# MOTOR_DRIVER_L298N.net
KiCad netlist of a schematic drawn in EAGLE
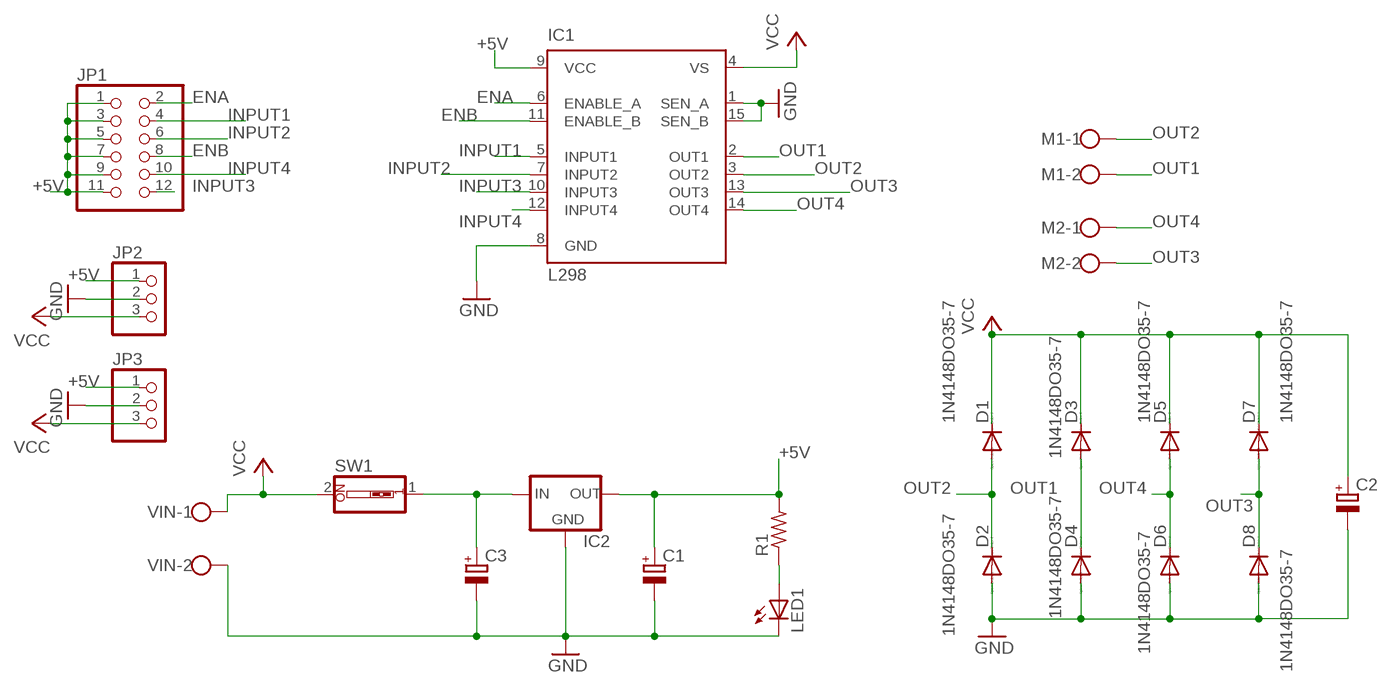
[diagram p0: schematic, sheet 1]

(export (version "E")
  (design (tool "Eeschema 10.0.6"))
  (components
    (comp (ref "C1")
      (value "CPOL-EUE5-6")
      (footprint "eagle-import:E5-6")
      (libsource (lib "eagle-import") (part "CPOL-EUE5-6"))
    )
    (comp (ref "C2")
      (value "CPOL-EUE5-6")
      (footprint "eagle-import:E5-6")
      (libsource (lib "eagle-import") (part "CPOL-EUE5-6"))
    )
    (comp (ref "C3")
      (value "CPOL-EUE5-6")
      (footprint "eagle-import:E5-6")
      (libsource (lib "eagle-import") (part "CPOL-EUE5-6"))
    )
    (comp (ref "D1")
      (value "1N4148DO35-7")
      (footprint "eagle-import:DO35-7")
      (libsource (lib "eagle-import") (part "1N4148DO35-7"))
    )
    (comp (ref "D2")
      (value "1N4148DO35-7")
      (footprint "eagle-import:DO35-7")
      (libsource (lib "eagle-import") (part "1N4148DO35-7"))
    )
    (comp (ref "D3")
      (value "1N4148DO35-7")
      (footprint "eagle-import:DO35-7")
      (libsource (lib "eagle-import") (part "1N4148DO35-7"))
    )
    (comp (ref "D4")
      (value "1N4148DO35-7")
      (footprint "eagle-import:DO35-7")
      (libsource (lib "eagle-import") (part "1N4148DO35-7"))
    )
    (comp (ref "D5")
      (value "1N4148DO35-7")
      (footprint "eagle-import:DO35-7")
      (libsource (lib "eagle-import") (part "1N4148DO35-7"))
    )
    (comp (ref "D6")
      (value "1N4148DO35-7")
      (footprint "eagle-import:DO35-7")
      (libsource (lib "eagle-import") (part "1N4148DO35-7"))
    )
    (comp (ref "D7")
      (value "1N4148DO35-7")
      (footprint "eagle-import:DO35-7")
      (libsource (lib "eagle-import") (part "1N4148DO35-7"))
    )
    (comp (ref "D8")
      (value "1N4148DO35-7")
      (footprint "eagle-import:DO35-7")
      (libsource (lib "eagle-import") (part "1N4148DO35-7"))
    )
    (comp (ref "IC1")
      (value "L298")
      (footprint "eagle-import:MULTIWATT-15")
      (fields (field (name "MPN") "L298N"))
      (libsource (lib "eagle-import") (part "L298"))
    )
    (comp (ref "IC2")
      (value "78MXXS")
      (footprint "eagle-import:78MXXS")
      (libsource (lib "eagle-import") (part "78MXXS"))
    )
    (comp (ref "JP1")
      (value "PINHD-2X6")
      (footprint "eagle-import:2X06")
      (libsource (lib "eagle-import") (part "PINHD-2X6"))
    )
    (comp (ref "JP2")
      (value "PINHD-1X3")
      (footprint "eagle-import:1X03")
      (libsource (lib "eagle-import") (part "PINHD-1X3"))
    )
    (comp (ref "JP3")
      (value "PINHD-1X3")
      (footprint "eagle-import:1X03")
      (libsource (lib "eagle-import") (part "PINHD-1X3"))
    )
    (comp (ref "LED1")
      (value "LED5MM")
      (footprint "eagle-import:LED5MM")
      (libsource (lib "eagle-import") (part "LED5MM"))
    )
    (comp (ref "M1")
      (value "W237-102")
      (footprint "eagle-import:W237-102")
      (fields (field (name "MPN") "237-102"))
      (libsource (lib "eagle-import") (part "W237-102"))
    )
    (comp (ref "M2")
      (value "W237-102")
      (footprint "eagle-import:W237-102")
      (fields (field (name "MPN") "237-102"))
      (libsource (lib "eagle-import") (part "W237-102"))
    )
    (comp (ref "R1")
      (value "R-US_0204/7")
      (footprint "eagle-import:0204_7")
      (libsource (lib "eagle-import") (part "R-US_0204/7"))
    )
    (comp (ref "SW1")
      (value "SW_DIP-1")
      (footprint "eagle-import:EDG-01")
      (libsource (lib "eagle-import") (part "SW_DIP-1"))
    )
    (comp (ref "VIN")
      (value "W237-102")
      (footprint "eagle-import:W237-102")
      (fields (field (name "MPN") "237-102"))
      (libsource (lib "eagle-import") (part "W237-102"))
    )
  )
  (nets
    (net (code "1") (name "/+5V") (class "Default")
      (node (ref "C1") (pin "+") (pinfunction "+_+") (pintype "passive"))
      (node (ref "IC1") (pin "9") (pinfunction "VCC_9") (pintype "power_in"))
      (node (ref "IC2") (pin "OUT") (pinfunction "OUT_OUT") (pintype "passive"))
      (node (ref "JP1") (pin "1") (pinfunction "1_1") (pintype "passive"))
      (node (ref "JP1") (pin "11") (pinfunction "11_11") (pintype "passive"))
      (node (ref "JP1") (pin "3") (pinfunction "3_3") (pintype "passive"))
      (node (ref "JP1") (pin "5") (pinfunction "5_5") (pintype "passive"))
      (node (ref "JP1") (pin "7") (pinfunction "7_7") (pintype "passive"))
      (node (ref "JP1") (pin "9") (pinfunction "9_9") (pintype "passive"))
      (node (ref "JP2") (pin "1") (pinfunction "1_1") (pintype "passive"))
      (node (ref "JP3") (pin "1") (pinfunction "1_1") (pintype "passive"))
      (node (ref "R1") (pin "2") (pinfunction "2_2") (pintype "passive"))
    )
    (net (code "2") (name "/ENA") (class "Default")
      (node (ref "IC1") (pin "6") (pinfunction "ENABLE_A_6") (pintype "input"))
      (node (ref "JP1") (pin "2") (pinfunction "2_2") (pintype "passive"))
    )
    (net (code "3") (name "/ENB") (class "Default")
      (node (ref "IC1") (pin "11") (pinfunction "ENABLE_B_11") (pintype "input"))
      (node (ref "JP1") (pin "8") (pinfunction "8_8") (pintype "passive"))
    )
    (net (code "4") (name "/INPUT1") (class "Default")
      (node (ref "IC1") (pin "5") (pinfunction "INPUT1_5") (pintype "input"))
      (node (ref "JP1") (pin "4") (pinfunction "4_4") (pintype "passive"))
    )
    (net (code "5") (name "/INPUT2") (class "Default")
      (node (ref "IC1") (pin "7") (pinfunction "INPUT2_7") (pintype "input"))
      (node (ref "JP1") (pin "6") (pinfunction "6_6") (pintype "passive"))
    )
    (net (code "6") (name "/INPUT3") (class "Default")
      (node (ref "IC1") (pin "10") (pinfunction "INPUT3_10") (pintype "input"))
      (node (ref "JP1") (pin "12") (pinfunction "12_12") (pintype "passive"))
    )
    (net (code "7") (name "/INPUT4") (class "Default")
      (node (ref "IC1") (pin "12") (pinfunction "INPUT4_12") (pintype "input"))
      (node (ref "JP1") (pin "10") (pinfunction "10_10") (pintype "passive"))
    )
    (net (code "8") (name "/OUT1") (class "Default")
      (node (ref "D3") (pin "A") (pinfunction "A_A") (pintype "passive"))
      (node (ref "D4") (pin "C") (pinfunction "C_C") (pintype "passive"))
      (node (ref "IC1") (pin "2") (pinfunction "OUT1_2") (pintype "output"))
      (node (ref "M1") (pin "2") (pinfunction "KL_2") (pintype "passive"))
    )
    (net (code "9") (name "/OUT2") (class "Default")
      (node (ref "D1") (pin "A") (pinfunction "A_A") (pintype "passive"))
      (node (ref "D2") (pin "C") (pinfunction "C_C") (pintype "passive"))
      (node (ref "IC1") (pin "3") (pinfunction "OUT2_3") (pintype "output"))
      (node (ref "M1") (pin "1") (pinfunction "KL_1") (pintype "passive"))
    )
    (net (code "10") (name "/OUT3") (class "Default")
      (node (ref "D7") (pin "A") (pinfunction "A_A") (pintype "passive"))
      (node (ref "D8") (pin "C") (pinfunction "C_C") (pintype "passive"))
      (node (ref "IC1") (pin "13") (pinfunction "OUT3_13") (pintype "output"))
      (node (ref "M2") (pin "2") (pinfunction "KL_2") (pintype "passive"))
    )
    (net (code "11") (name "/OUT4") (class "Default")
      (node (ref "D5") (pin "A") (pinfunction "A_A") (pintype "passive"))
      (node (ref "D6") (pin "C") (pinfunction "C_C") (pintype "passive"))
      (node (ref "IC1") (pin "14") (pinfunction "OUT4_14") (pintype "output"))
      (node (ref "M2") (pin "1") (pinfunction "KL_1") (pintype "passive"))
    )
    (net (code "12") (name "GND") (class "Default")
      (node (ref "C1") (pin "-") (pinfunction "-_-") (pintype "passive"))
      (node (ref "C2") (pin "-") (pinfunction "-_-") (pintype "passive"))
      (node (ref "C3") (pin "-") (pinfunction "-_-") (pintype "passive"))
      (node (ref "D2") (pin "A") (pinfunction "A_A") (pintype "passive"))
      (node (ref "D4") (pin "A") (pinfunction "A_A") (pintype "passive"))
      (node (ref "D6") (pin "A") (pinfunction "A_A") (pintype "passive"))
      (node (ref "D8") (pin "A") (pinfunction "A_A") (pintype "passive"))
      (node (ref "IC1") (pin "1") (pinfunction "SEN_A_1") (pintype "input"))
      (node (ref "IC1") (pin "15") (pinfunction "SEN_B_15") (pintype "input"))
      (node (ref "IC1") (pin "8") (pinfunction "GND_8") (pintype "power_in"))
      (node (ref "IC2") (pin "GND") (pinfunction "GND_GND") (pintype "input"))
      (node (ref "JP2") (pin "2") (pinfunction "2_2") (pintype "passive"))
      (node (ref "JP3") (pin "2") (pinfunction "2_2") (pintype "passive"))
      (node (ref "LED1") (pin "K") (pinfunction "C_K") (pintype "passive"))
      (node (ref "VIN") (pin "2") (pinfunction "KL_2") (pintype "passive"))
    )
    (net (code "13") (name "Net-(C3-Pad+)") (class "Default")
      (node (ref "C3") (pin "+") (pinfunction "+_+") (pintype "passive"))
      (node (ref "IC2") (pin "IN") (pinfunction "IN_IN") (pintype "input"))
      (node (ref "SW1") (pin "1") (pinfunction "1_1") (pintype "passive"))
    )
    (net (code "14") (name "Net-(LED1-PadA)") (class "Default")
      (node (ref "LED1") (pin "A") (pinfunction "A_A") (pintype "passive"))
      (node (ref "R1") (pin "1") (pinfunction "1_1") (pintype "passive"))
    )
    (net (code "15") (name "VCC") (class "Default")
      (node (ref "C2") (pin "+") (pinfunction "+_+") (pintype "passive"))
      (node (ref "D1") (pin "C") (pinfunction "C_C") (pintype "passive"))
      (node (ref "D3") (pin "C") (pinfunction "C_C") (pintype "passive"))
      (node (ref "D5") (pin "C") (pinfunction "C_C") (pintype "passive"))
      (node (ref "D7") (pin "C") (pinfunction "C_C") (pintype "passive"))
      (node (ref "IC1") (pin "4") (pinfunction "VS_4") (pintype "power_in"))
      (node (ref "JP2") (pin "3") (pinfunction "3_3") (pintype "passive"))
      (node (ref "JP3") (pin "3") (pinfunction "3_3") (pintype "passive"))
      (node (ref "SW1") (pin "2") (pinfunction "2_2") (pintype "passive"))
      (node (ref "VIN") (pin "1") (pinfunction "KL_1") (pintype "passive"))
    )
  )
)
